# serre_light_v2.net
KiCad netlist of a schematic drawn in EAGLE
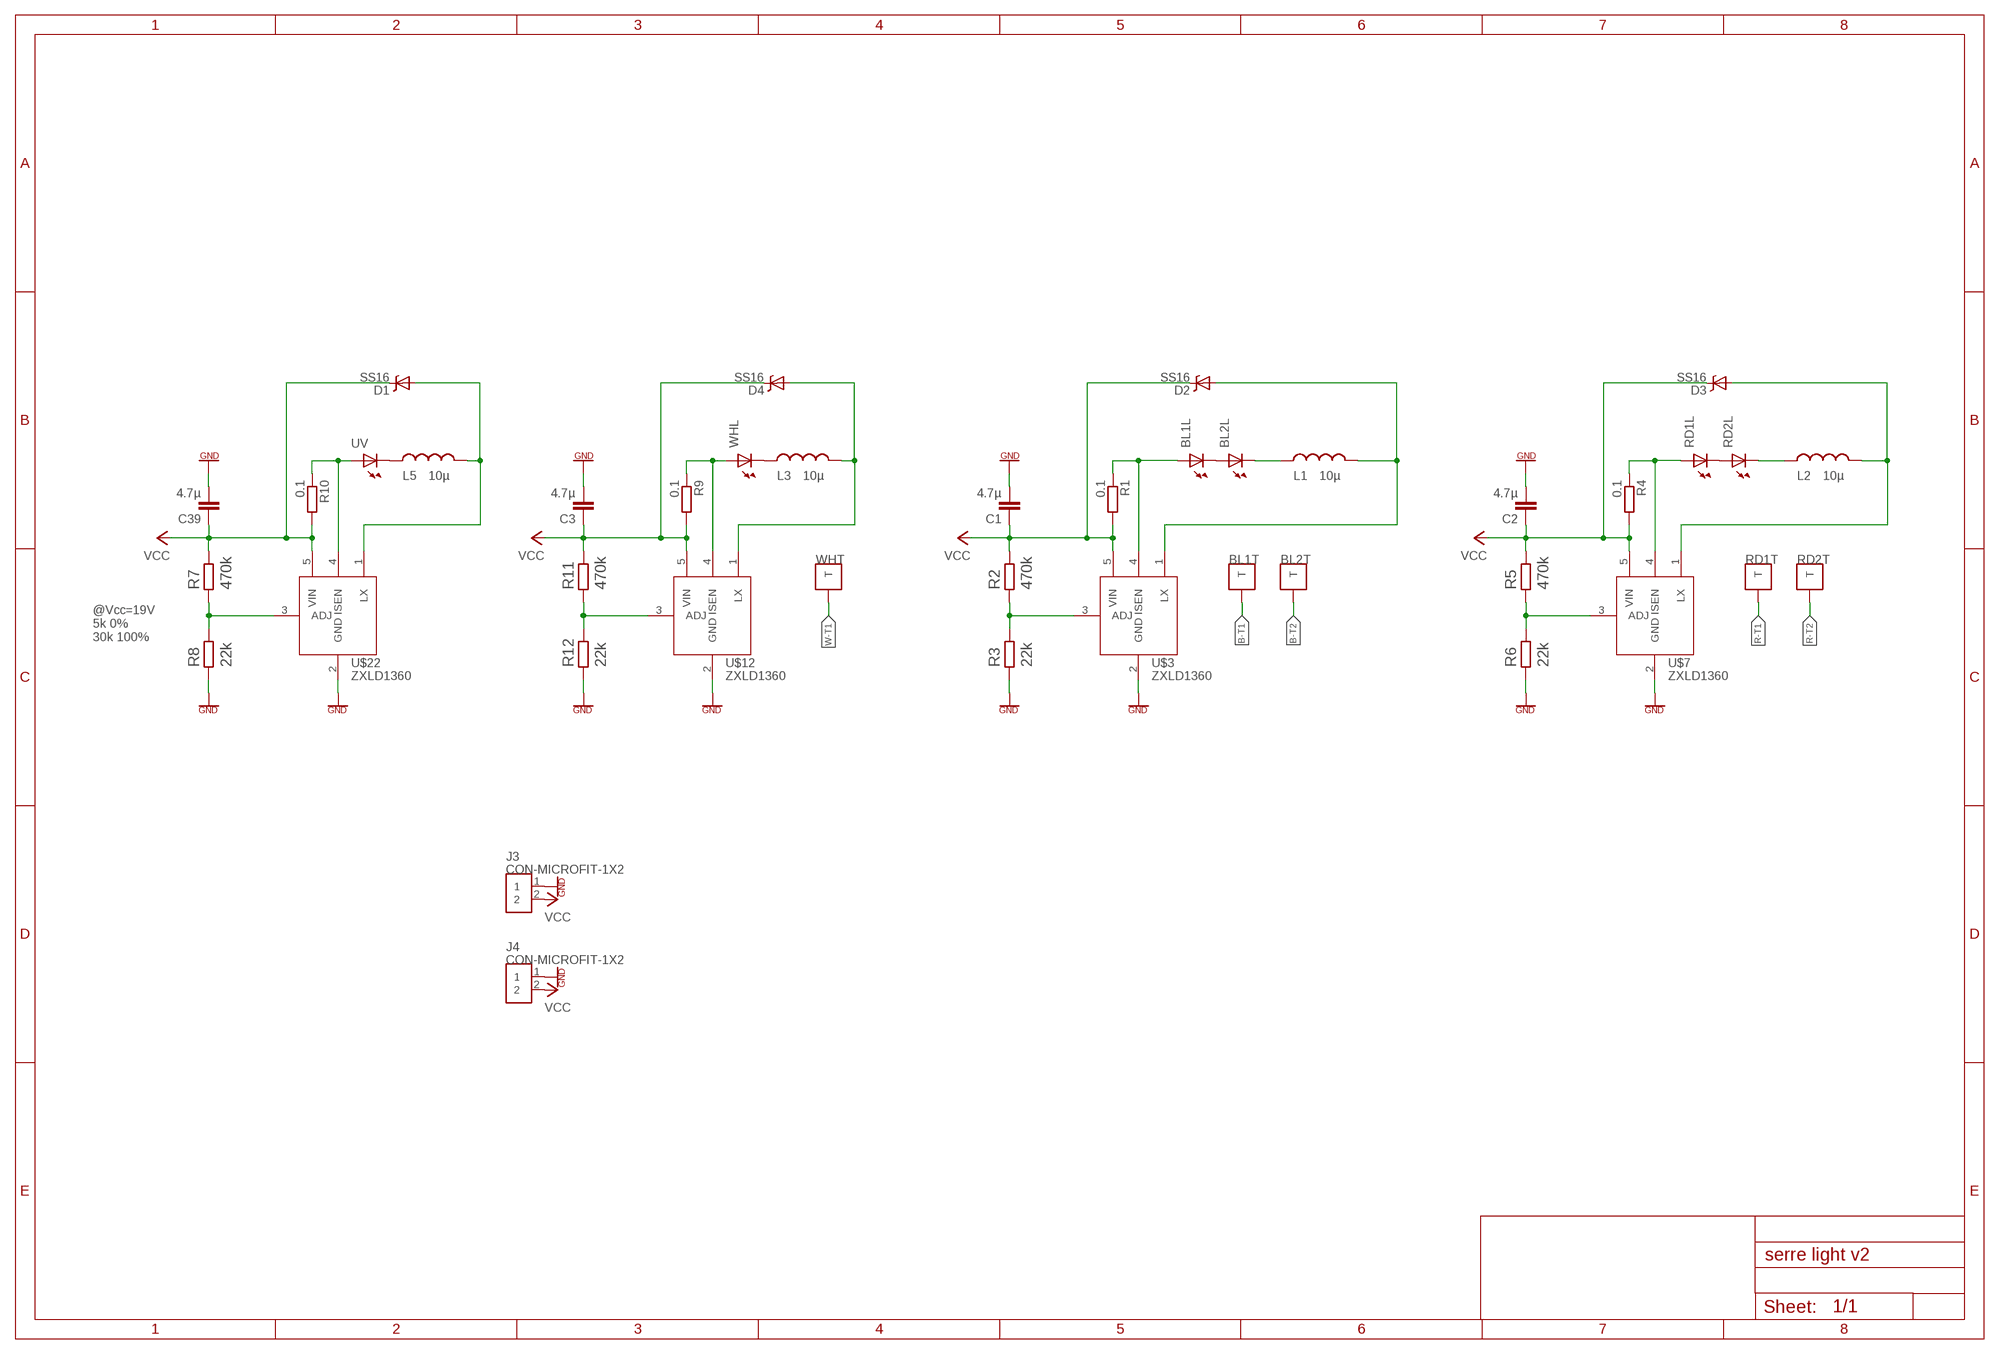
[diagram p0: schematic, sheet 1]

(export (version "E")
  (design (tool "Eeschema 10.0.6"))
  (components
    (comp (ref "BL1")
      (value "LED-THERMAL-CREE-GP-G3")
      (footprint "eagle-import:LED-CREE-GP-G3")
      (fields (field (name "MPN") "XPGDRY-L1-0000-00601"))
      (libsource (lib "eagle-import") (part "LED-THERMAL-CREE-GP-G3"))
    )
    (comp (ref "BL2")
      (value "LED-THERMAL-CREE-GP-G3")
      (footprint "eagle-import:LED-CREE-GP-G3")
      (fields (field (name "MPN") "XPGDRY-L1-0000-00601"))
      (libsource (lib "eagle-import") (part "LED-THERMAL-CREE-GP-G3"))
    )
    (comp (ref "C1")
      (value "4.7µ")
      (footprint "eagle-import:C1210")
      (libsource (lib "eagle-import") (part "C-EUC1210"))
    )
    (comp (ref "C2")
      (value "4.7µ")
      (footprint "eagle-import:C1210")
      (libsource (lib "eagle-import") (part "C-EUC1210"))
    )
    (comp (ref "C3")
      (value "4.7µ")
      (footprint "eagle-import:C1210")
      (libsource (lib "eagle-import") (part "C-EUC1210"))
    )
    (comp (ref "C39")
      (value "4.7µ")
      (footprint "eagle-import:C1210")
      (libsource (lib "eagle-import") (part "C-EUC1210"))
    )
    (comp (ref "D1")
      (value "SS16")
      (footprint "eagle-import:SS16_DIODE")
      (libsource (lib "eagle-import") (part "DIODE_SCHOTTKY_SS16"))
    )
    (comp (ref "D2")
      (value "SS16")
      (footprint "eagle-import:SS16_DIODE")
      (libsource (lib "eagle-import") (part "DIODE_SCHOTTKY_SS16"))
    )
    (comp (ref "D3")
      (value "SS16")
      (footprint "eagle-import:SS16_DIODE")
      (libsource (lib "eagle-import") (part "DIODE_SCHOTTKY_SS16"))
    )
    (comp (ref "D4")
      (value "SS16")
      (footprint "eagle-import:SS16_DIODE")
      (libsource (lib "eagle-import") (part "DIODE_SCHOTTKY_SS16"))
    )
    (comp (ref "J3")
      (value "CON-MICROFIT-1X2")
      (footprint "eagle-import:MICROFIT-1X2")
      (libsource (lib "eagle-import") (part "CON-MICROFIT-1X2"))
    )
    (comp (ref "J4")
      (value "CON-MICROFIT-1X2")
      (footprint "eagle-import:MICROFIT-1X2")
      (libsource (lib "eagle-import") (part "CON-MICROFIT-1X2"))
    )
    (comp (ref "L1")
      (value "10µ")
      (footprint "eagle-import:SRN5040TA")
      (libsource (lib "eagle-import") (part "LSRN5040TA"))
    )
    (comp (ref "L2")
      (value "10µ")
      (footprint "eagle-import:SRN5040TA")
      (libsource (lib "eagle-import") (part "LSRN5040TA"))
    )
    (comp (ref "L3")
      (value "10µ")
      (footprint "eagle-import:SRN5040TA")
      (libsource (lib "eagle-import") (part "LSRN5040TA"))
    )
    (comp (ref "L5")
      (value "10µ")
      (footprint "eagle-import:SRN5040TA")
      (libsource (lib "eagle-import") (part "LSRN5040TA"))
    )
    (comp (ref "R1")
      (value "0.1")
      (footprint "eagle-import:R1206")
      (libsource (lib "eagle-import") (part "R-EU_R1206"))
    )
    (comp (ref "R2")
      (value "470k")
      (footprint "eagle-import:R0805")
      (libsource (lib "eagle-import") (part "R0805"))
    )
    (comp (ref "R3")
      (value "22k")
      (footprint "eagle-import:R0805")
      (libsource (lib "eagle-import") (part "R0805"))
    )
    (comp (ref "R4")
      (value "0.1")
      (footprint "eagle-import:R1206")
      (libsource (lib "eagle-import") (part "R-EU_R1206"))
    )
    (comp (ref "R5")
      (value "470k")
      (footprint "eagle-import:R0805")
      (libsource (lib "eagle-import") (part "R0805"))
    )
    (comp (ref "R6")
      (value "22k")
      (footprint "eagle-import:R0805")
      (libsource (lib "eagle-import") (part "R0805"))
    )
    (comp (ref "R7")
      (value "470k")
      (footprint "eagle-import:R0805")
      (libsource (lib "eagle-import") (part "R0805"))
    )
    (comp (ref "R8")
      (value "22k")
      (footprint "eagle-import:R0805")
      (libsource (lib "eagle-import") (part "R0805"))
    )
    (comp (ref "R9")
      (value "0.1")
      (footprint "eagle-import:R1206")
      (libsource (lib "eagle-import") (part "R-EU_R1206"))
    )
    (comp (ref "R10")
      (value "0.1")
      (footprint "eagle-import:R1206")
      (libsource (lib "eagle-import") (part "R-EU_R1206"))
    )
    (comp (ref "R11")
      (value "470k")
      (footprint "eagle-import:R0805")
      (libsource (lib "eagle-import") (part "R0805"))
    )
    (comp (ref "R12")
      (value "22k")
      (footprint "eagle-import:R0805")
      (libsource (lib "eagle-import") (part "R0805"))
    )
    (comp (ref "RD1")
      (value "LED-THERMAL-LUMINU-SST-10-DR")
      (footprint "eagle-import:LED-LUMINU-SST-10-DR")
      (libsource (lib "eagle-import") (part "LED-THERMAL-LUMINU-SST-10-DR"))
    )
    (comp (ref "RD2")
      (value "LED-THERMAL-LUMINU-SST-10-DR")
      (footprint "eagle-import:LED-LUMINU-SST-10-DR")
      (libsource (lib "eagle-import") (part "LED-THERMAL-LUMINU-SST-10-DR"))
    )
    (comp (ref "U$3")
      (value "ZXLD1360")
      (footprint "eagle-import:SOT23-5L")
      (libsource (lib "eagle-import") (part "ZXLD1360"))
    )
    (comp (ref "U$7")
      (value "ZXLD1360")
      (footprint "eagle-import:SOT23-5L")
      (libsource (lib "eagle-import") (part "ZXLD1360"))
    )
    (comp (ref "U$12")
      (value "ZXLD1360")
      (footprint "eagle-import:SOT23-5L")
      (libsource (lib "eagle-import") (part "ZXLD1360"))
    )
    (comp (ref "U$22")
      (value "ZXLD1360")
      (footprint "eagle-import:SOT23-5L")
      (libsource (lib "eagle-import") (part "ZXLD1360"))
    )
    (comp (ref "UV")
      (value "LED-LUXEON-UV-U2")
      (footprint "eagle-import:LED-LUXEON-UV-U2")
      (libsource (lib "eagle-import") (part "LED-LUXEON-UV-U2"))
    )
    (comp (ref "WH")
      (value "LED-THERMAL-OSRAM-GW")
      (footprint "eagle-import:LED-OSRAM-GW")
      (fields (field (name "MPN") "GW CS8PM1.PM-LSLU-XX52-1"))
      (libsource (lib "eagle-import") (part "LED-THERMAL-OSRAM-GW"))
    )
  )
  (nets
    (net (code "1") (name "B-T1") (class "Default")
      (node (ref "BL1") (pin "THERMAL") (pinfunction "T_THERMAL") (pintype "bidirectional"))
    )
    (net (code "2") (name "B-T2") (class "Default")
      (node (ref "BL2") (pin "THERMAL") (pinfunction "T_THERMAL") (pintype "bidirectional"))
    )
    (net (code "3") (name "GND") (class "Default")
      (node (ref "C1") (pin "2") (pinfunction "2_2") (pintype "passive"))
      (node (ref "C2") (pin "2") (pinfunction "2_2") (pintype "passive"))
      (node (ref "C3") (pin "2") (pinfunction "2_2") (pintype "passive"))
      (node (ref "C39") (pin "2") (pinfunction "2_2") (pintype "passive"))
      (node (ref "J3") (pin "1") (pinfunction "1_1") (pintype "bidirectional"))
      (node (ref "J4") (pin "1") (pinfunction "1_1") (pintype "bidirectional"))
      (node (ref "R12") (pin "1") (pinfunction "1_1") (pintype "bidirectional"))
      (node (ref "R3") (pin "1") (pinfunction "1_1") (pintype "bidirectional"))
      (node (ref "R6") (pin "1") (pinfunction "1_1") (pintype "bidirectional"))
      (node (ref "R8") (pin "1") (pinfunction "1_1") (pintype "bidirectional"))
      (node (ref "U$12") (pin "2") (pinfunction "GND_2") (pintype "bidirectional"))
      (node (ref "U$22") (pin "2") (pinfunction "GND_2") (pintype "bidirectional"))
      (node (ref "U$3") (pin "2") (pinfunction "GND_2") (pintype "bidirectional"))
      (node (ref "U$7") (pin "2") (pinfunction "GND_2") (pintype "bidirectional"))
    )
    (net (code "4") (name "Net-(BL1-PadC)") (class "Default")
      (node (ref "BL1") (pin "C") (pinfunction "C_C") (pintype "passive"))
      (node (ref "BL2") (pin "A") (pinfunction "A_A") (pintype "passive"))
    )
    (net (code "5") (name "Net-(L1-1)") (class "Default")
      (node (ref "BL2") (pin "C") (pinfunction "C_C") (pintype "passive"))
      (node (ref "L1") (pin "P$1") (pinfunction "1_P$1") (pintype "bidirectional"))
    )
    (net (code "6") (name "Net-(L1-2)") (class "Default")
      (node (ref "D2") (pin "A") (pinfunction "A_A") (pintype "passive"))
      (node (ref "L1") (pin "P$2") (pinfunction "2_P$2") (pintype "bidirectional"))
      (node (ref "U$3") (pin "1") (pinfunction "LX_1") (pintype "bidirectional"))
    )
    (net (code "7") (name "Net-(L2-1)") (class "Default")
      (node (ref "L2") (pin "P$1") (pinfunction "1_P$1") (pintype "bidirectional"))
      (node (ref "RD2") (pin "C") (pinfunction "C_C") (pintype "passive"))
    )
    (net (code "8") (name "Net-(L2-2)") (class "Default")
      (node (ref "D3") (pin "A") (pinfunction "A_A") (pintype "passive"))
      (node (ref "L2") (pin "P$2") (pinfunction "2_P$2") (pintype "bidirectional"))
      (node (ref "U$7") (pin "1") (pinfunction "LX_1") (pintype "bidirectional"))
    )
    (net (code "9") (name "Net-(L3-1)") (class "Default")
      (node (ref "L3") (pin "P$1") (pinfunction "1_P$1") (pintype "bidirectional"))
      (node (ref "WH") (pin "C") (pinfunction "C_C") (pintype "passive"))
    )
    (net (code "10") (name "Net-(L3-2)") (class "Default")
      (node (ref "D4") (pin "A") (pinfunction "A_A") (pintype "passive"))
      (node (ref "L3") (pin "P$2") (pinfunction "2_P$2") (pintype "bidirectional"))
      (node (ref "U$12") (pin "1") (pinfunction "LX_1") (pintype "bidirectional"))
    )
    (net (code "11") (name "Net-(L5-1)") (class "Default")
      (node (ref "L5") (pin "P$1") (pinfunction "1_P$1") (pintype "bidirectional"))
      (node (ref "UV") (pin "C") (pinfunction "C_C") (pintype "passive"))
    )
    (net (code "12") (name "Net-(L5-2)") (class "Default")
      (node (ref "D1") (pin "A") (pinfunction "A_A") (pintype "passive"))
      (node (ref "L5") (pin "P$2") (pinfunction "2_P$2") (pintype "bidirectional"))
      (node (ref "U$22") (pin "1") (pinfunction "LX_1") (pintype "bidirectional"))
    )
    (net (code "13") (name "Net-(RD1-PadC)") (class "Default")
      (node (ref "RD1") (pin "C") (pinfunction "C_C") (pintype "passive"))
      (node (ref "RD2") (pin "A") (pinfunction "A_A") (pintype "passive"))
    )
    (net (code "14") (name "Net-(U$3-ADJ)") (class "Default")
      (node (ref "R2") (pin "1") (pinfunction "1_1") (pintype "bidirectional"))
      (node (ref "R3") (pin "2") (pinfunction "2_2") (pintype "bidirectional"))
      (node (ref "U$3") (pin "3") (pinfunction "ADJ_3") (pintype "bidirectional"))
    )
    (net (code "15") (name "Net-(U$3-ISEN)") (class "Default")
      (node (ref "BL1") (pin "A") (pinfunction "A_A") (pintype "passive"))
      (node (ref "R1") (pin "1") (pinfunction "1_1") (pintype "passive"))
      (node (ref "U$3") (pin "4") (pinfunction "ISEN_4") (pintype "bidirectional"))
    )
    (net (code "16") (name "Net-(U$7-ADJ)") (class "Default")
      (node (ref "R5") (pin "1") (pinfunction "1_1") (pintype "bidirectional"))
      (node (ref "R6") (pin "2") (pinfunction "2_2") (pintype "bidirectional"))
      (node (ref "U$7") (pin "3") (pinfunction "ADJ_3") (pintype "bidirectional"))
    )
    (net (code "17") (name "Net-(U$7-ISEN)") (class "Default")
      (node (ref "R4") (pin "1") (pinfunction "1_1") (pintype "passive"))
      (node (ref "RD1") (pin "A") (pinfunction "A_A") (pintype "passive"))
      (node (ref "U$7") (pin "4") (pinfunction "ISEN_4") (pintype "bidirectional"))
    )
    (net (code "18") (name "Net-(U$12-ADJ)") (class "Default")
      (node (ref "R11") (pin "1") (pinfunction "1_1") (pintype "bidirectional"))
      (node (ref "R12") (pin "2") (pinfunction "2_2") (pintype "bidirectional"))
      (node (ref "U$12") (pin "3") (pinfunction "ADJ_3") (pintype "bidirectional"))
    )
    (net (code "19") (name "Net-(U$12-ISEN)") (class "Default")
      (node (ref "R9") (pin "1") (pinfunction "1_1") (pintype "passive"))
      (node (ref "U$12") (pin "4") (pinfunction "ISEN_4") (pintype "bidirectional"))
      (node (ref "WH") (pin "A") (pinfunction "A_A") (pintype "passive"))
    )
    (net (code "20") (name "Net-(U$22-ADJ)") (class "Default")
      (node (ref "R7") (pin "1") (pinfunction "1_1") (pintype "bidirectional"))
      (node (ref "R8") (pin "2") (pinfunction "2_2") (pintype "bidirectional"))
      (node (ref "U$22") (pin "3") (pinfunction "ADJ_3") (pintype "bidirectional"))
    )
    (net (code "21") (name "Net-(U$22-ISEN)") (class "Default")
      (node (ref "R10") (pin "1") (pinfunction "1_1") (pintype "passive"))
      (node (ref "U$22") (pin "4") (pinfunction "ISEN_4") (pintype "bidirectional"))
      (node (ref "UV") (pin "A") (pinfunction "A_A") (pintype "passive"))
    )
    (net (code "22") (name "R-T1") (class "Default")
      (node (ref "RD1") (pin "THERMAL") (pinfunction "T_THERMAL") (pintype "bidirectional"))
    )
    (net (code "23") (name "R-T2") (class "Default")
      (node (ref "RD2") (pin "THERMAL") (pinfunction "T_THERMAL") (pintype "bidirectional"))
    )
    (net (code "24") (name "VCC") (class "Default")
      (node (ref "C1") (pin "1") (pinfunction "1_1") (pintype "passive"))
      (node (ref "C2") (pin "1") (pinfunction "1_1") (pintype "passive"))
      (node (ref "C3") (pin "1") (pinfunction "1_1") (pintype "passive"))
      (node (ref "C39") (pin "1") (pinfunction "1_1") (pintype "passive"))
      (node (ref "D1") (pin "K") (pinfunction "C_K") (pintype "passive"))
      (node (ref "D2") (pin "K") (pinfunction "C_K") (pintype "passive"))
      (node (ref "D3") (pin "K") (pinfunction "C_K") (pintype "passive"))
      (node (ref "D4") (pin "K") (pinfunction "C_K") (pintype "passive"))
      (node (ref "J3") (pin "2") (pinfunction "2_2") (pintype "bidirectional"))
      (node (ref "J4") (pin "2") (pinfunction "2_2") (pintype "bidirectional"))
      (node (ref "R1") (pin "2") (pinfunction "2_2") (pintype "passive"))
      (node (ref "R10") (pin "2") (pinfunction "2_2") (pintype "passive"))
      (node (ref "R11") (pin "2") (pinfunction "2_2") (pintype "bidirectional"))
      (node (ref "R2") (pin "2") (pinfunction "2_2") (pintype "bidirectional"))
      (node (ref "R4") (pin "2") (pinfunction "2_2") (pintype "passive"))
      (node (ref "R5") (pin "2") (pinfunction "2_2") (pintype "bidirectional"))
      (node (ref "R7") (pin "2") (pinfunction "2_2") (pintype "bidirectional"))
      (node (ref "R9") (pin "2") (pinfunction "2_2") (pintype "passive"))
      (node (ref "U$12") (pin "5") (pinfunction "VIN_5") (pintype "bidirectional"))
      (node (ref "U$22") (pin "5") (pinfunction "VIN_5") (pintype "bidirectional"))
      (node (ref "U$3") (pin "5") (pinfunction "VIN_5") (pintype "bidirectional"))
      (node (ref "U$7") (pin "5") (pinfunction "VIN_5") (pintype "bidirectional"))
    )
    (net (code "25") (name "W-T1") (class "Default")
      (node (ref "WH") (pin "THERMAL") (pinfunction "T_THERMAL") (pintype "bidirectional"))
    )
  )
)
